# FAIO2_Switch.net
KiCad netlist of a schematic drawn in EAGLE
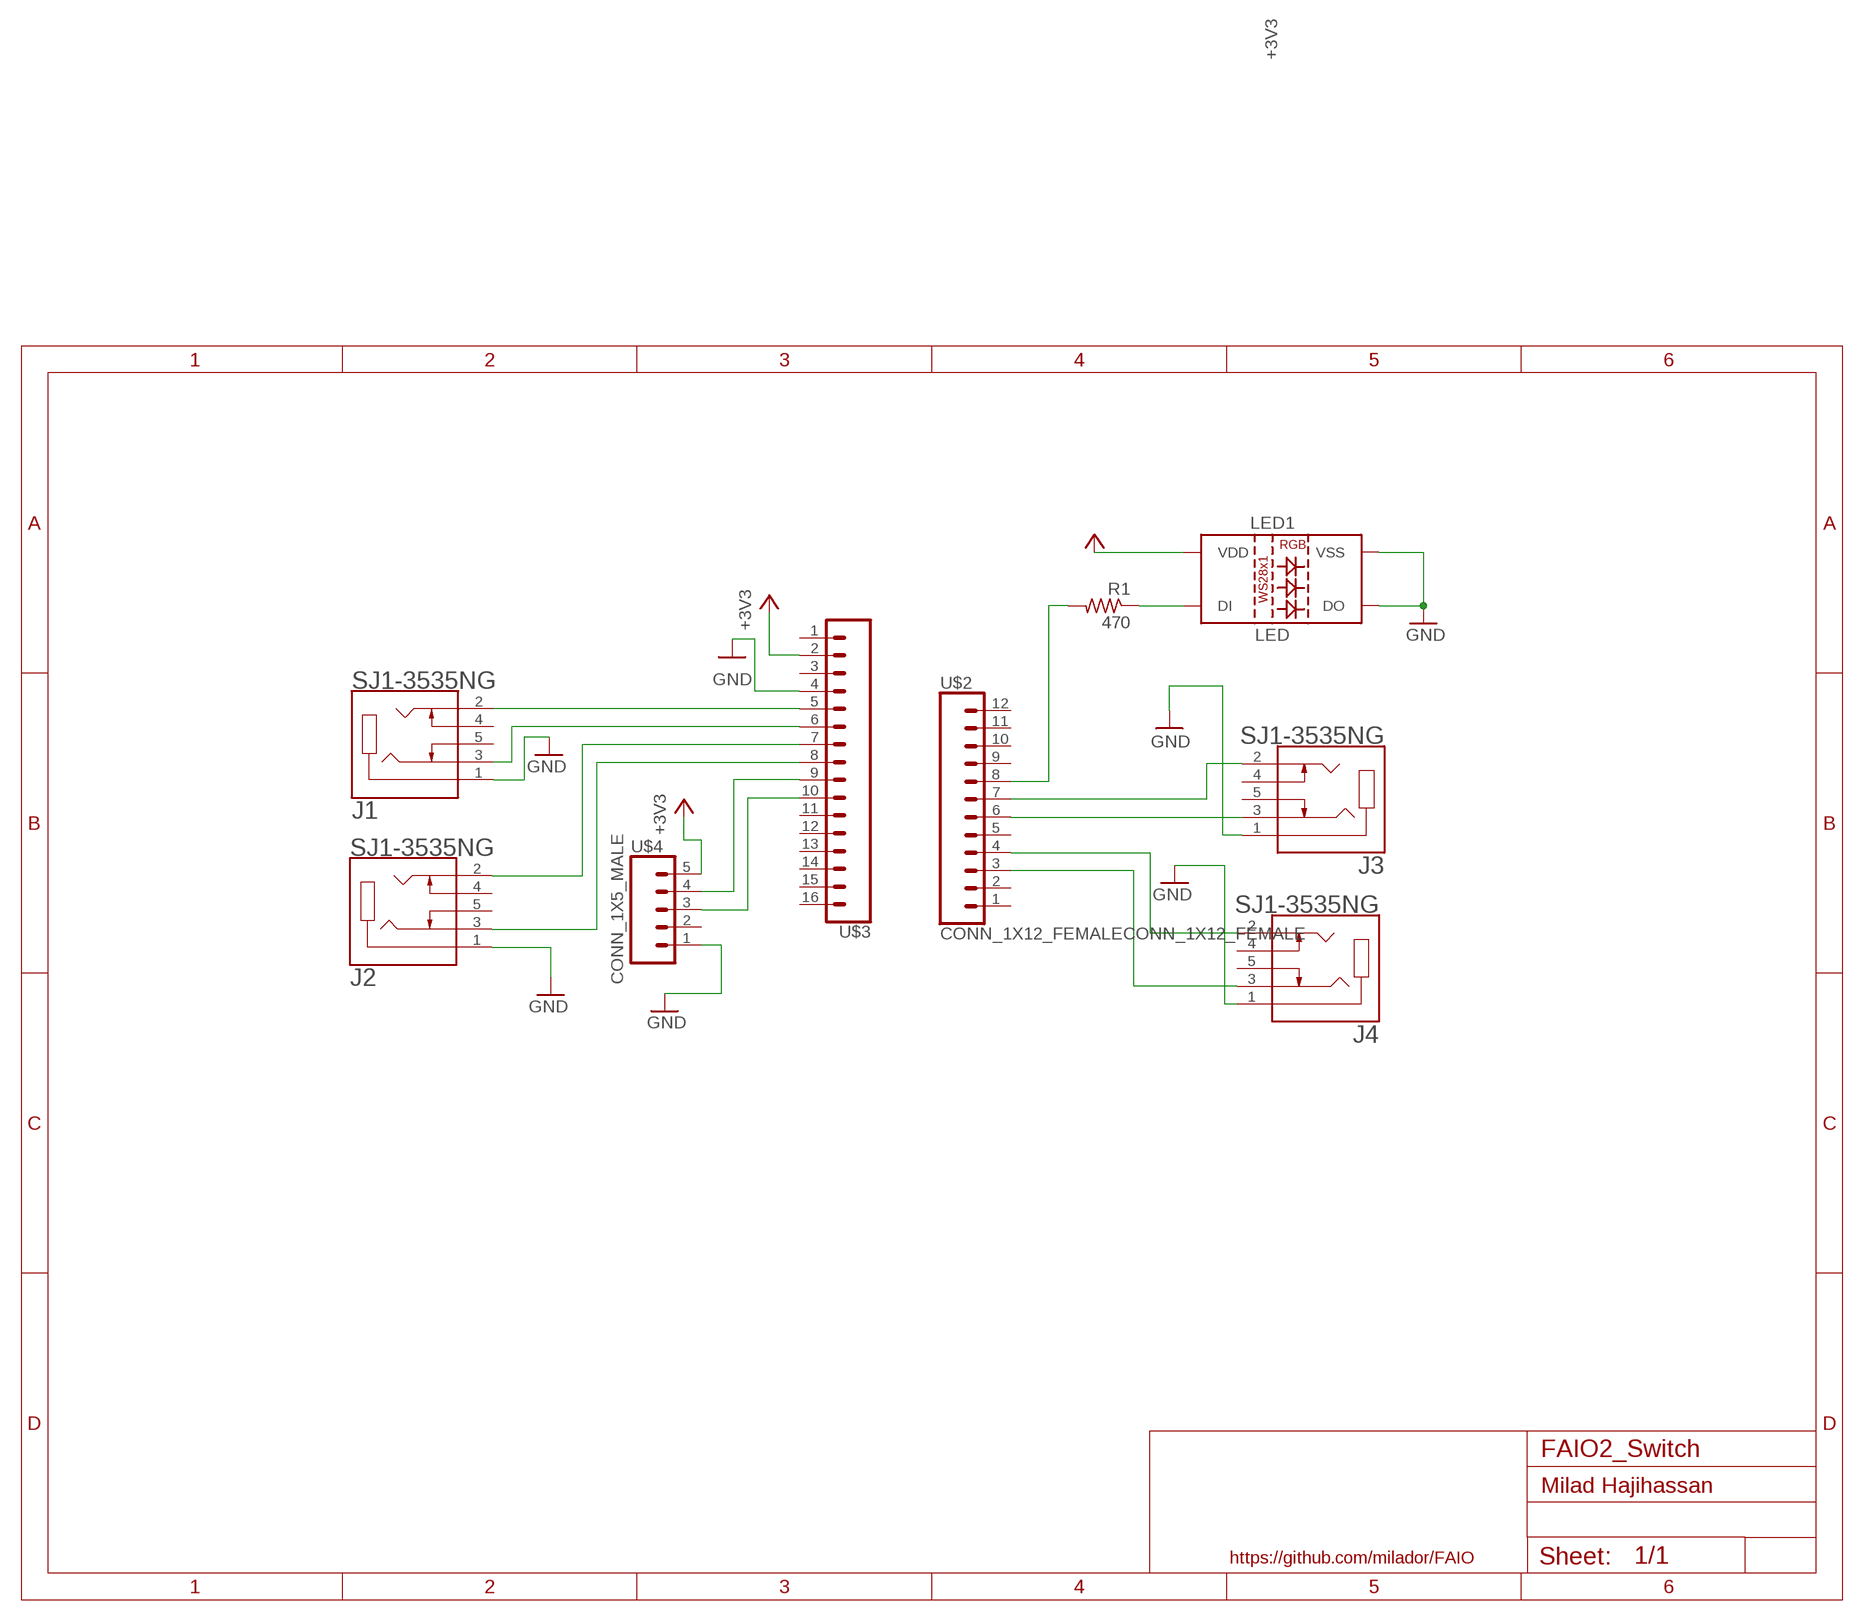
[diagram p0: schematic, sheet 1]

(export (version "E")
  (design (tool "Eeschema 10.0.6"))
  (components
    (comp (ref "J1")
      (value "SJ1-3535NG")
      (footprint "eagle-import:CUI_SJ1-3535NG")
      (fields (field (name "MANUFACTURER") "CUI"))
      (libsource (lib "eagle-import") (part "SJ1-3535NG"))
    )
    (comp (ref "J2")
      (value "SJ1-3535NG")
      (footprint "eagle-import:CUI_SJ1-3535NG")
      (fields (field (name "MANUFACTURER") "CUI"))
      (libsource (lib "eagle-import") (part "SJ1-3535NG"))
    )
    (comp (ref "J3")
      (value "SJ1-3535NG")
      (footprint "eagle-import:CUI_SJ1-3535NG")
      (fields (field (name "MANUFACTURER") "CUI"))
      (libsource (lib "eagle-import") (part "SJ1-3535NG"))
    )
    (comp (ref "J4")
      (value "SJ1-3535NG")
      (footprint "eagle-import:CUI_SJ1-3535NG")
      (fields (field (name "MANUFACTURER") "CUI"))
      (libsource (lib "eagle-import") (part "SJ1-3535NG"))
    )
    (comp (ref "LED1")
      (value "LED")
      (footprint "eagle-import:NEOPIXELS-5MM")
      (libsource (lib "eagle-import") (part "NEOPIXELS-5MM"))
    )
    (comp (ref "R1")
      (value "470")
      (footprint "eagle-import:0204_7")
      (libsource (lib "eagle-import") (part "R-US_0204/7"))
    )
    (comp (ref "U$2")
      (value "CONN_1X12_FEMALECONN_1X12_FEMALE")
      (footprint "eagle-import:CONN_1X12")
      (libsource (lib "eagle-import") (part "CONN_1X12_FEMALECONN_1X12_FEMALE"))
    )
    (comp (ref "U$3")
      (value "CONN_1X16_FEMALECONN_1X16_FEMALE")
      (footprint "eagle-import:CONN_1X16")
      (libsource (lib "eagle-import") (part "CONN_1X16_FEMALECONN_1X16_FEMALE"))
    )
    (comp (ref "U$4")
      (value "CONN_1X5_MALE")
      (footprint "eagle-import:CONN_1X5")
      (libsource (lib "eagle-import") (part "CONN_1X5_MALE"))
    )
  )
  (nets
    (net (code "1") (name "+3V3") (class "Default")
      (node (ref "LED1") (pin "2") (pinfunction "VDD_2") (pintype "bidirectional"))
      (node (ref "U$3") (pin "2") (pinfunction "2_2") (pintype "passive"))
      (node (ref "U$4") (pin "5") (pinfunction "5_5") (pintype "passive"))
    )
    (net (code "2") (name "GND") (class "Default")
      (node (ref "J1") (pin "1") (pinfunction "1_1") (pintype "passive"))
      (node (ref "J2") (pin "1") (pinfunction "1_1") (pintype "passive"))
      (node (ref "J3") (pin "1") (pinfunction "1_1") (pintype "passive"))
      (node (ref "J4") (pin "1") (pinfunction "1_1") (pintype "passive"))
      (node (ref "LED1") (pin "3") (pinfunction "VSS_3") (pintype "bidirectional"))
      (node (ref "LED1") (pin "4") (pinfunction "DO_4") (pintype "bidirectional"))
      (node (ref "U$3") (pin "4") (pinfunction "4_4") (pintype "passive"))
      (node (ref "U$4") (pin "1") (pinfunction "1_1") (pintype "passive"))
    )
    (net (code "3") (name "Net-(J1-Pad2)") (class "Default")
      (node (ref "J1") (pin "2") (pinfunction "2_2") (pintype "passive"))
      (node (ref "U$3") (pin "5") (pinfunction "5_5") (pintype "passive"))
    )
    (net (code "4") (name "Net-(J1-Pad3)") (class "Default")
      (node (ref "J1") (pin "3") (pinfunction "3_3") (pintype "passive"))
      (node (ref "U$3") (pin "6") (pinfunction "6_6") (pintype "passive"))
    )
    (net (code "5") (name "Net-(J2-Pad2)") (class "Default")
      (node (ref "J2") (pin "2") (pinfunction "2_2") (pintype "passive"))
      (node (ref "U$3") (pin "7") (pinfunction "7_7") (pintype "passive"))
    )
    (net (code "6") (name "Net-(J2-Pad3)") (class "Default")
      (node (ref "J2") (pin "3") (pinfunction "3_3") (pintype "passive"))
      (node (ref "U$3") (pin "8") (pinfunction "8_8") (pintype "passive"))
    )
    (net (code "7") (name "Net-(J3-Pad2)") (class "Default")
      (node (ref "J3") (pin "2") (pinfunction "2_2") (pintype "passive"))
      (node (ref "U$2") (pin "7") (pinfunction "7_7") (pintype "passive"))
    )
    (net (code "8") (name "Net-(J3-Pad3)") (class "Default")
      (node (ref "J3") (pin "3") (pinfunction "3_3") (pintype "passive"))
      (node (ref "U$2") (pin "6") (pinfunction "6_6") (pintype "passive"))
    )
    (net (code "9") (name "Net-(J4-Pad2)") (class "Default")
      (node (ref "J4") (pin "2") (pinfunction "2_2") (pintype "passive"))
      (node (ref "U$2") (pin "4") (pinfunction "4_4") (pintype "passive"))
    )
    (net (code "10") (name "Net-(J4-Pad3)") (class "Default")
      (node (ref "J4") (pin "3") (pinfunction "3_3") (pintype "passive"))
      (node (ref "U$2") (pin "3") (pinfunction "3_3") (pintype "passive"))
    )
    (net (code "11") (name "Net-(LED1-DI)") (class "Default")
      (node (ref "LED1") (pin "1") (pinfunction "DI_1") (pintype "bidirectional"))
      (node (ref "R1") (pin "1") (pinfunction "1_1") (pintype "passive"))
    )
    (net (code "12") (name "Net-(R1-Pad2)") (class "Default")
      (node (ref "R1") (pin "2") (pinfunction "2_2") (pintype "passive"))
      (node (ref "U$2") (pin "8") (pinfunction "8_8") (pintype "passive"))
    )
    (net (code "13") (name "Net-(U$3-Pad9)") (class "Default")
      (node (ref "U$3") (pin "9") (pinfunction "9_9") (pintype "passive"))
      (node (ref "U$4") (pin "4") (pinfunction "4_4") (pintype "passive"))
    )
    (net (code "14") (name "Net-(U$3-Pad10)") (class "Default")
      (node (ref "U$3") (pin "10") (pinfunction "10_10") (pintype "passive"))
      (node (ref "U$4") (pin "3") (pinfunction "3_3") (pintype "passive"))
    )
    (net (code "15") (name "unconnected-(J1-Pad4)") (class "Default")
      (node (ref "J1") (pin "4") (pinfunction "4_4") (pintype "passive"))
    )
    (net (code "16") (name "unconnected-(J1-Pad5)") (class "Default")
      (node (ref "J1") (pin "5") (pinfunction "5_5") (pintype "passive"))
    )
    (net (code "17") (name "unconnected-(J2-Pad4)") (class "Default")
      (node (ref "J2") (pin "4") (pinfunction "4_4") (pintype "passive"))
    )
    (net (code "18") (name "unconnected-(J2-Pad5)") (class "Default")
      (node (ref "J2") (pin "5") (pinfunction "5_5") (pintype "passive"))
    )
    (net (code "19") (name "unconnected-(J3-Pad4)") (class "Default")
      (node (ref "J3") (pin "4") (pinfunction "4_4") (pintype "passive"))
    )
    (net (code "20") (name "unconnected-(J3-Pad5)") (class "Default")
      (node (ref "J3") (pin "5") (pinfunction "5_5") (pintype "passive"))
    )
    (net (code "21") (name "unconnected-(J4-Pad4)") (class "Default")
      (node (ref "J4") (pin "4") (pinfunction "4_4") (pintype "passive"))
    )
    (net (code "22") (name "unconnected-(J4-Pad5)") (class "Default")
      (node (ref "J4") (pin "5") (pinfunction "5_5") (pintype "passive"))
    )
    (net (code "23") (name "unconnected-(U$2-Pad1)") (class "Default")
      (node (ref "U$2") (pin "1") (pinfunction "1_1") (pintype "passive"))
    )
    (net (code "24") (name "unconnected-(U$2-Pad2)") (class "Default")
      (node (ref "U$2") (pin "2") (pinfunction "2_2") (pintype "passive"))
    )
    (net (code "25") (name "unconnected-(U$2-Pad5)") (class "Default")
      (node (ref "U$2") (pin "5") (pinfunction "5_5") (pintype "passive"))
    )
    (net (code "26") (name "unconnected-(U$2-Pad9)") (class "Default")
      (node (ref "U$2") (pin "9") (pinfunction "9_9") (pintype "passive"))
    )
    (net (code "27") (name "unconnected-(U$2-Pad10)") (class "Default")
      (node (ref "U$2") (pin "10") (pinfunction "10_10") (pintype "passive"))
    )
    (net (code "28") (name "unconnected-(U$2-Pad11)") (class "Default")
      (node (ref "U$2") (pin "11") (pinfunction "11_11") (pintype "passive"))
    )
    (net (code "29") (name "unconnected-(U$2-Pad12)") (class "Default")
      (node (ref "U$2") (pin "12") (pinfunction "12_12") (pintype "passive"))
    )
    (net (code "30") (name "unconnected-(U$3-Pad1)") (class "Default")
      (node (ref "U$3") (pin "1") (pinfunction "1_1") (pintype "passive"))
    )
    (net (code "31") (name "unconnected-(U$3-Pad3)") (class "Default")
      (node (ref "U$3") (pin "3") (pinfunction "3_3") (pintype "passive"))
    )
    (net (code "32") (name "unconnected-(U$3-Pad11)") (class "Default")
      (node (ref "U$3") (pin "11") (pinfunction "11_11") (pintype "passive"))
    )
    (net (code "33") (name "unconnected-(U$3-Pad12)") (class "Default")
      (node (ref "U$3") (pin "12") (pinfunction "12_12") (pintype "passive"))
    )
    (net (code "34") (name "unconnected-(U$3-Pad13)") (class "Default")
      (node (ref "U$3") (pin "13") (pinfunction "13_13") (pintype "passive"))
    )
    (net (code "35") (name "unconnected-(U$3-Pad14)") (class "Default")
      (node (ref "U$3") (pin "14") (pinfunction "14_14") (pintype "passive"))
    )
    (net (code "36") (name "unconnected-(U$3-Pad15)") (class "Default")
      (node (ref "U$3") (pin "15") (pinfunction "15_15") (pintype "passive"))
    )
    (net (code "37") (name "unconnected-(U$3-Pad16)") (class "Default")
      (node (ref "U$3") (pin "16") (pinfunction "16_16") (pintype "passive"))
    )
    (net (code "38") (name "unconnected-(U$4-Pad2)") (class "Default")
      (node (ref "U$4") (pin "2") (pinfunction "2_2") (pintype "passive"))
    )
  )
)
